# DSO_Front.net
KiCad netlist of a schematic drawn in Altium Designer
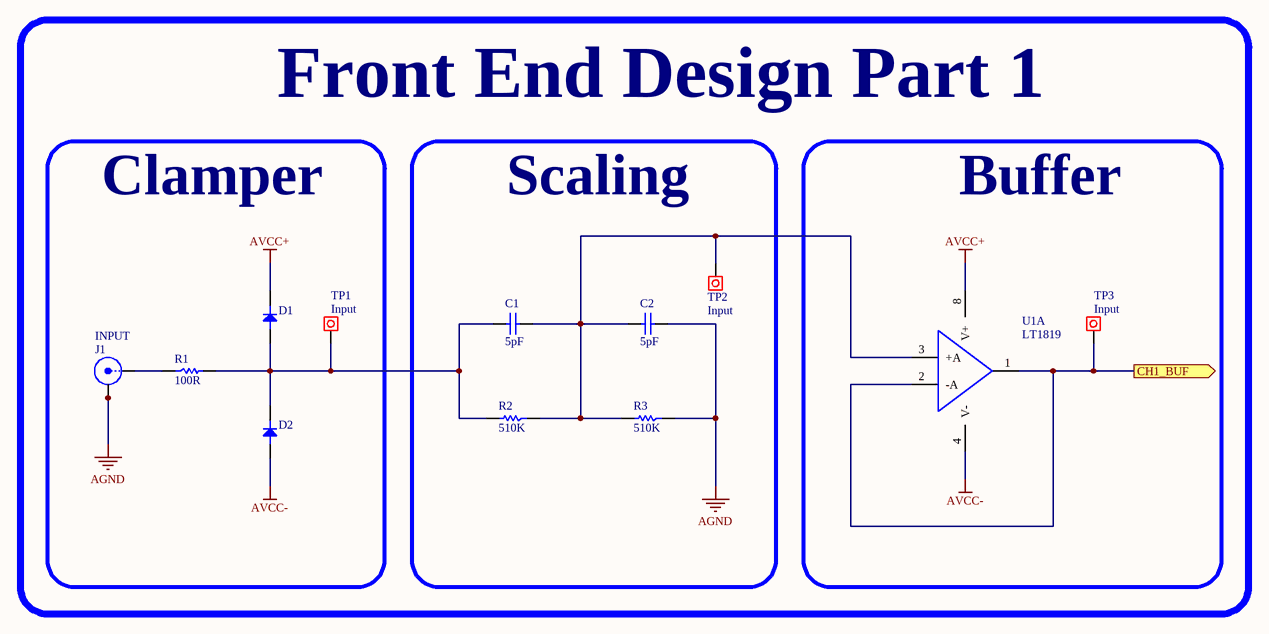
[diagram p0: DSO_Front.SchDoc]

(export (version "E")
  (design (tool "Eeschema 10.0.6"))
  (components
    (comp (ref "C1")
      (value "5pF")
      (footprint "0805C")
      (description "Capacitor")
      (fields (field (name "REVIEWED BY") "RM - 2018/08/05"))
      (libsource (lib "DSO") (part "C"))
    )
    (comp (ref "C2")
      (value "5pF")
      (footprint "0805C")
      (description "Capacitor")
      (fields (field (name "REVIEWED BY") "RM - 2018/08/05"))
      (libsource (lib "DSO") (part "C"))
    )
    (comp (ref "D1")
      (value "Diode")
      (footprint "SOD-123")
      (fields (field (name "REVIEWED BY") "RM - 2018/08/05"))
      (libsource (lib "DSO") (part "D"))
    )
    (comp (ref "D2")
      (value "Diode")
      (footprint "SOD-123")
      (fields (field (name "REVIEWED BY") "RM - 2018/08/05"))
      (libsource (lib "DSO") (part "D"))
    )
    (comp (ref "J1")
      (value "INPUT")
      (footprint "BNC_VERT")
      (description "BNC Straight")
      (fields (field (name "REVIEWED BY") "RM - 2018/08/05"))
      (libsource (lib "DSO") (part "BNC"))
    )
    (comp (ref "R1")
      (value "100R")
      (footprint "0805")
      (description "Resistor")
      (fields (field (name "REVIEWED BY") "RM - 2018/08/05"))
      (libsource (lib "DSO") (part "R"))
    )
    (comp (ref "R2")
      (value "510K")
      (footprint "0805")
      (description "Resistor")
      (fields (field (name "REVIEWED BY") "RM - 2018/08/05"))
      (libsource (lib "DSO") (part "R"))
    )
    (comp (ref "R3")
      (value "510K")
      (footprint "0805")
      (description "Resistor")
      (fields (field (name "REVIEWED BY") "RM - 2018/08/05"))
      (libsource (lib "DSO") (part "R"))
    )
    (comp (ref "TP1")
      (value "Input")
      (footprint "Testpoin")
      (description "Pad")
      (fields (field (name "Comment") "INPUT"))
      (libsource (lib "DSO") (part "Test Point"))
    )
    (comp (ref "TP2")
      (value "Input")
      (footprint "Testpoin")
      (description "Pad")
      (fields (field (name "Comment") "INPUT"))
      (libsource (lib "DSO") (part "Test Point"))
    )
    (comp (ref "TP3")
      (value "Input")
      (footprint "Testpoin")
      (description "Pad")
      (fields (field (name "Comment") "INPUT"))
      (libsource (lib "DSO") (part "Test Point"))
    )
    (comp (ref "U1")
      (value "LT1819")
      (footprint "SOIC-8")
      (description "OpAmp High Frequency Dual")
      (fields (field (name "REVIEWED BY") "RM - 2018/08/05"))
      (libsource (lib "DSO") (part "LT1819"))
    )
  )
  (nets
    (net (code "1") (name "/CH1_BUF") (class "Default")
      (node (ref "TP3") (pin "1") (pintype "passive"))
      (node (ref "U1") (pin "1") (pinfunction "OUTA_1") (pintype "passive"))
      (node (ref "U1") (pin "2") (pinfunction "-A_2") (pintype "passive"))
    )
    (net (code "2") (name "AGND") (class "Default")
      (node (ref "C2") (pin "1") (pinfunction "1_1") (pintype "passive"))
      (node (ref "J1") (pin "2") (pinfunction "Y_2") (pintype "passive"))
      (node (ref "J1") (pin "3") (pinfunction "Y_3") (pintype "passive"))
      (node (ref "J1") (pin "4") (pinfunction "Y_4") (pintype "passive"))
      (node (ref "J1") (pin "5") (pinfunction "Y_5") (pintype "passive"))
      (node (ref "R3") (pin "1") (pintype "passive"))
    )
    (net (code "3") (name "AVCC+") (class "Default")
      (node (ref "D1") (pin "K") (pinfunction "K_K") (pintype "passive"))
      (node (ref "U1") (pin "8") (pinfunction "V+_8") (pintype "passive"))
    )
    (net (code "4") (name "AVCC-") (class "Default")
      (node (ref "D2") (pin "A") (pinfunction "A_A") (pintype "passive"))
      (node (ref "U1") (pin "4") (pinfunction "V-_4") (pintype "passive"))
    )
    (net (code "5") (name "Net-(C1-Pad2)") (class "Default")
      (node (ref "C1") (pin "2") (pinfunction "2_2") (pintype "passive"))
      (node (ref "D1") (pin "A") (pinfunction "A_A") (pintype "passive"))
      (node (ref "D2") (pin "K") (pinfunction "K_K") (pintype "passive"))
      (node (ref "R1") (pin "2") (pintype "passive"))
      (node (ref "R2") (pin "2") (pintype "passive"))
      (node (ref "TP1") (pin "1") (pintype "passive"))
    )
    (net (code "6") (name "Net-(J1-X)") (class "Default")
      (node (ref "J1") (pin "1") (pinfunction "X_1") (pintype "passive"))
      (node (ref "R1") (pin "1") (pintype "passive"))
    )
    (net (code "7") (name "Net-(U1A-+A)") (class "Default")
      (node (ref "C1") (pin "1") (pinfunction "1_1") (pintype "passive"))
      (node (ref "C2") (pin "2") (pinfunction "2_2") (pintype "passive"))
      (node (ref "R2") (pin "1") (pintype "passive"))
      (node (ref "R3") (pin "2") (pintype "passive"))
      (node (ref "TP2") (pin "1") (pintype "passive"))
      (node (ref "U1") (pin "3") (pinfunction "+A_3") (pintype "passive"))
    )
  )
)
